# controlerV2.net
KiCad netlist of a schematic drawn in EAGLE
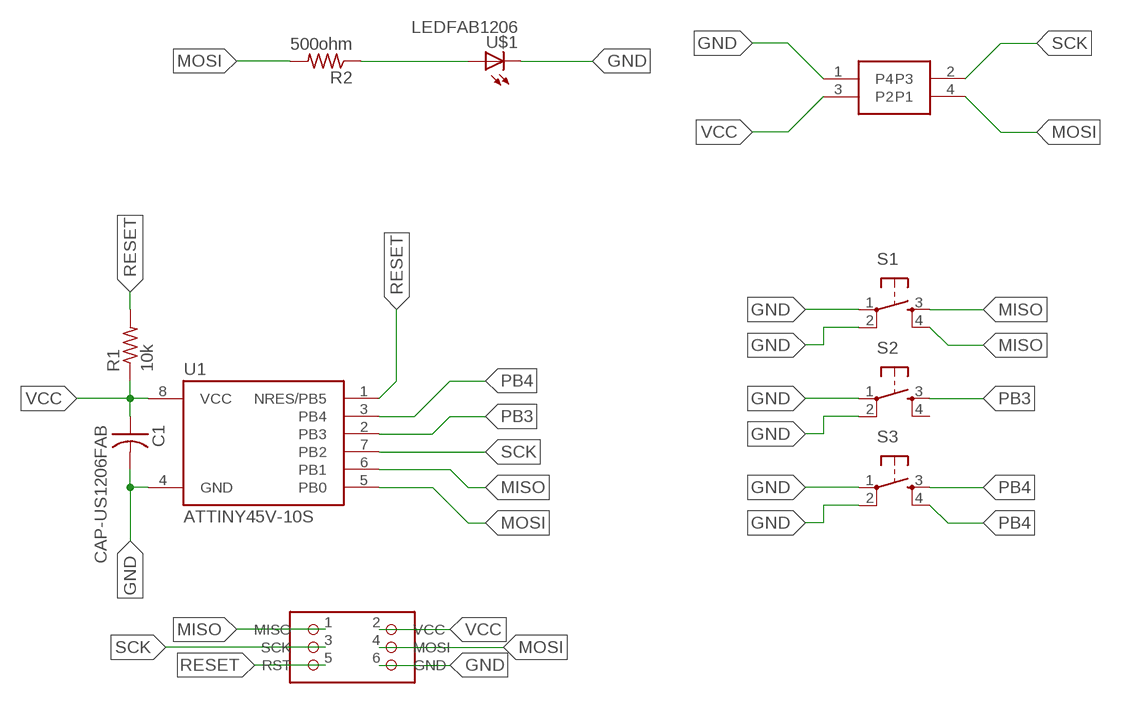
[diagram p0: schematic, sheet 1]

(export (version "E")
  (design (tool "Eeschema 10.0.6"))
  (components
    (comp (ref "C1")
      (value "CAP-US1206FAB")
      (footprint "eagle-import:C1206FAB")
      (libsource (lib "eagle-import") (part "CAP-US1206FAB"))
    )
    (comp (ref "R1")
      (value "10k")
      (footprint "eagle-import:R1206")
      (libsource (lib "eagle-import") (part "R-US_R1206"))
    )
    (comp (ref "R2")
      (value "500ohm")
      (footprint "eagle-import:R1206FAB")
      (libsource (lib "eagle-import") (part "RES-US1206FAB"))
    )
    (comp (ref "S1")
      (value "6MM_SWITCH6MM_SWITCH")
      (footprint "eagle-import:6MM_SWITCH")
      (libsource (lib "eagle-import") (part "6MM_SWITCH6MM_SWITCH"))
    )
    (comp (ref "S2")
      (value "6MM_SWITCH6MM_SWITCH")
      (footprint "eagle-import:6MM_SWITCH")
      (libsource (lib "eagle-import") (part "6MM_SWITCH6MM_SWITCH"))
    )
    (comp (ref "S3")
      (value "6MM_SWITCH6MM_SWITCH")
      (footprint "eagle-import:6MM_SWITCH")
      (libsource (lib "eagle-import") (part "6MM_SWITCH6MM_SWITCH"))
    )
    (comp (ref "U$1")
      (value "LEDFAB1206")
      (footprint "eagle-import:LED1206FAB")
      (libsource (lib "eagle-import") (part "LEDFAB1206"))
    )
    (comp (ref "U$2")
      (value "4PIN-SMD-CONNECTOR")
      (footprint "eagle-import:2X02SMD")
      (libsource (lib "eagle-import") (part "4PIN-SMD-CONNECTOR"))
    )
    (comp (ref "U$4")
      (value "AVRISPSMD")
      (footprint "eagle-import:2X03SMD")
      (libsource (lib "eagle-import") (part "AVRISPSMD"))
    )
    (comp (ref "U1")
      (value "ATTINY45V-10S")
      (footprint "eagle-import:SOIC8_EIAJ_208MIL")
      (libsource (lib "eagle-import") (part "ATTINY45SV-10"))
    )
  )
  (nets
    (net (code "1") (name "GND") (class "Default")
      (node (ref "C1") (pin "2") (pinfunction "2_2") (pintype "passive"))
      (node (ref "S1") (pin "1") (pinfunction "P_1") (pintype "passive"))
      (node (ref "S1") (pin "2") (pinfunction "P1_2") (pintype "passive"))
      (node (ref "S2") (pin "1") (pinfunction "P_1") (pintype "passive"))
      (node (ref "S2") (pin "2") (pinfunction "P1_2") (pintype "passive"))
      (node (ref "S3") (pin "1") (pinfunction "P_1") (pintype "passive"))
      (node (ref "S3") (pin "2") (pinfunction "P1_2") (pintype "passive"))
      (node (ref "U$1") (pin "2") (pinfunction "C_2") (pintype "passive"))
      (node (ref "U$2") (pin "1") (pinfunction "P4_1") (pintype "bidirectional"))
      (node (ref "U$4") (pin "6") (pinfunction "GND_6") (pintype "passive"))
      (node (ref "U1") (pin "4") (pinfunction "GND_4") (pintype "power_in"))
    )
    (net (code "2") (name "MISO") (class "Default")
      (node (ref "S1") (pin "3") (pinfunction "S_3") (pintype "passive"))
      (node (ref "S1") (pin "4") (pinfunction "S1_4") (pintype "passive"))
      (node (ref "U$4") (pin "1") (pinfunction "MISO_1") (pintype "passive"))
      (node (ref "U1") (pin "6") (pinfunction "PB1_6") (pintype "bidirectional"))
    )
    (net (code "3") (name "MOSI") (class "Default")
      (node (ref "R2") (pin "2") (pinfunction "2_2") (pintype "passive"))
      (node (ref "U$2") (pin "4") (pinfunction "P1_4") (pintype "bidirectional"))
      (node (ref "U$4") (pin "4") (pinfunction "MOSI_4") (pintype "passive"))
      (node (ref "U1") (pin "5") (pinfunction "PB0_5") (pintype "bidirectional"))
    )
    (net (code "4") (name "Net-(U$1-A)") (class "Default")
      (node (ref "R2") (pin "1") (pinfunction "1_1") (pintype "passive"))
      (node (ref "U$1") (pin "1") (pinfunction "A_1") (pintype "passive"))
    )
    (net (code "5") (name "PB3") (class "Default")
      (node (ref "S2") (pin "3") (pinfunction "S_3") (pintype "passive"))
      (node (ref "U1") (pin "2") (pinfunction "PB3_2") (pintype "bidirectional"))
    )
    (net (code "6") (name "PB4") (class "Default")
      (node (ref "S3") (pin "3") (pinfunction "S_3") (pintype "passive"))
      (node (ref "S3") (pin "4") (pinfunction "S1_4") (pintype "passive"))
      (node (ref "U1") (pin "3") (pinfunction "PB4_3") (pintype "bidirectional"))
    )
    (net (code "7") (name "RESET") (class "Default")
      (node (ref "R1") (pin "2") (pinfunction "2_2") (pintype "passive"))
      (node (ref "U$4") (pin "5") (pinfunction "RST_5") (pintype "passive"))
      (node (ref "U1") (pin "1") (pinfunction "NRES/PB5_1") (pintype "bidirectional"))
    )
    (net (code "8") (name "SCK") (class "Default")
      (node (ref "U$2") (pin "2") (pinfunction "P3_2") (pintype "bidirectional"))
      (node (ref "U$4") (pin "3") (pinfunction "SCK_3") (pintype "passive"))
      (node (ref "U1") (pin "7") (pinfunction "PB2_7") (pintype "bidirectional"))
    )
    (net (code "9") (name "VCC") (class "Default")
      (node (ref "C1") (pin "1") (pinfunction "1_1") (pintype "passive"))
      (node (ref "R1") (pin "1") (pinfunction "1_1") (pintype "passive"))
      (node (ref "U$2") (pin "3") (pinfunction "P2_3") (pintype "bidirectional"))
      (node (ref "U$4") (pin "2") (pinfunction "VCC_2") (pintype "passive"))
      (node (ref "U1") (pin "8") (pinfunction "VCC_8") (pintype "power_in"))
    )
    (net (code "10") (name "unconnected-(S2-S1-Pad4)") (class "Default")
      (node (ref "S2") (pin "4") (pinfunction "S1_4") (pintype "passive"))
    )
  )
)
